# STEP-UP.net
KiCad netlist of a schematic drawn in Altium Designer
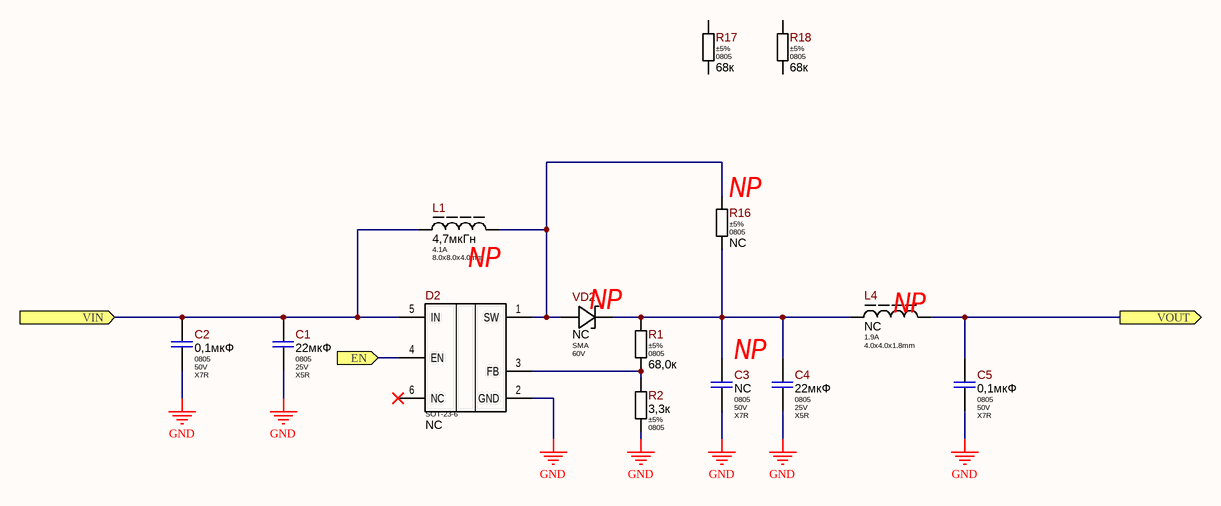
[diagram p0: STEP-UP.SchDoc]

(export (version "E")
  (design (tool "Eeschema 10.0.6"))
  (components
    (comp (ref "C1")
      (value "22мкФ")
      (footprint "CAP-0805(2012)X125T20")
      (description "22uF 25V X5R ±20% 0805 Ceramic Capacitor RoHS")
      (fields
        (field (name "PACKAGE") "0805")
        (field (name "VOLTAGE") "25V")
        (field (name "DIELECTRIC TYPE") "X5R")
        (field (name "PART NUMBER") "CL21A226MAYNNNE")
        (field (name "MANUFACTURER") "Samsung Electro-Mechanics")
      )
      (libsource (lib "capacitors") (part "CL21A226MAYNNNE"))
    )
    (comp (ref "C2")
      (value "0,1мкФ")
      (footprint "CAP-0805(2012)X85T10")
      (description "100nF 50V X7R ±10% 0805 Ceramic Capacitor RoHS")
      (fields
        (field (name "PACKAGE") "0805")
        (field (name "VOLTAGE") "50V")
        (field (name "DIELECTRIC TYPE") "X7R")
        (field (name "PART NUMBER") "CL21B104KBCNNNC")
        (field (name "MANUFACTURER") "Samsung Electro-Mechanics")
      )
      (libsource (lib "capacitors") (part "CL21B104KBCNNNC"))
    )
    (comp (ref "C3")
      (value "NC")
      (footprint "CAP-0805(2012)X85T10")
      (description "100nF 50V X7R ±10% 0805 Ceramic Capacitor RoHS")
      (fields
        (field (name "PACKAGE") "0805")
        (field (name "VOLTAGE") "50V")
        (field (name "DIELECTRIC TYPE") "X7R")
        (field (name "PART NUMBER") "CL21B104KBCNNNC")
        (field (name "MANUFACTURER") "Samsung Electro-Mechanics")
      )
      (libsource (lib "capacitors") (part "CL21B104KBCNNNC"))
    )
    (comp (ref "C4")
      (value "22мкФ")
      (footprint "CAP-0805(2012)X125T20")
      (description "22uF 25V X5R ±20% 0805 Ceramic Capacitor RoHS")
      (fields
        (field (name "PACKAGE") "0805")
        (field (name "VOLTAGE") "25V")
        (field (name "DIELECTRIC TYPE") "X5R")
        (field (name "PART NUMBER") "CL21A226MAYNNNE")
        (field (name "MANUFACTURER") "Samsung Electro-Mechanics")
      )
      (libsource (lib "capacitors") (part "CL21A226MAYNNNE"))
    )
    (comp (ref "C5")
      (value "0,1мкФ")
      (footprint "CAP-0805(2012)X85T10")
      (description "100nF 50V X7R ±10% 0805 Ceramic Capacitor RoHS")
      (fields
        (field (name "PACKAGE") "0805")
        (field (name "VOLTAGE") "50V")
        (field (name "DIELECTRIC TYPE") "X7R")
        (field (name "PART NUMBER") "CL21B104KBCNNNC")
        (field (name "MANUFACTURER") "Samsung Electro-Mechanics")
      )
      (libsource (lib "capacitors") (part "CL21B104KBCNNNC"))
    )
    (comp (ref "D2")
      (value "MT3608")
      (footprint "MT3608_MED")
      (description "2V-24V Input High Efficiency 1.2MHz 2A Step Up Converter")
      (fields
        (field (name "PACKAGE") "SOT-23-6")
        (field (name "PART NUMBER") "NC")
        (field (name "MANUFACTURER") "Aerosemi")
      )
      (libsource (lib "ic") (part "MT3608"))
    )
    (comp (ref "L1")
      (value "4,7мкГн")
      (footprint "SWPA8040S-Series")
      (description "4.7uH Magnetic-Resin Shielded Wirewound Inductor 4.1 A 25mOhm Max")
      (fields
        (field (name "CURRENT") "4.1A")
        (field (name "PACKAGE") "8.0x8.0x4.0mm")
        (field (name "PART NUMBER") "SWPA8040S4R7NT")
        (field (name "TOLERANCE") "±30%")
      )
      (libsource (lib "inductors") (part "SWPA8040S4R7NT"))
    )
    (comp (ref "L4")
      (value "NC")
      (footprint "SRN4018-Series_1.8mm")
      (description "4.7uH Semi-Shielded Wirewound Inductor 1.9A 84mOhm Max")
      (fields
        (field (name "CURRENT") "1.9A")
        (field (name "PACKAGE") "4.0x4.0x1.8mm")
        (field (name "PART NUMBER") "SRN4018-4R7M")
        (field (name "TOLERANCE") "±20%")
      )
      (libsource (lib "inductors") (part "SRN4018-4R7M"))
    )
    (comp (ref "R1")
      (value "68,0к")
      (footprint "R_ANY_CHIP_0805_MED")
      (description "2.2 kOhms ±5% 1/8W 0805 Thick Film Resistor")
      (fields
        (field (name "TOLERANCE") "±5%")
        (field (name "PACKAGE") "0805")
        (field (name "PART NUMBER") "RC0805JR-072K2L")
        (field (name "MANUFACTURER") "Yageo")
      )
      (libsource (lib "resistors") (part "RC0805JR-072K2L"))
    )
    (comp (ref "R2")
      (value "3,3к")
      (footprint "R_ANY_CHIP_0805_MED")
      (description "3.3 kOhms ±5%, 1/8W 0805 Thick Film Resistor")
      (fields
        (field (name "TOLERANCE") "±5%")
        (field (name "PACKAGE") "0805")
        (field (name "PART NUMBER") "RC0805JR-073K3L")
        (field (name "MANUFACTURER") "Yageo")
      )
      (libsource (lib "resistors") (part "RC0805JR-073K3L"))
    )
    (comp (ref "R16")
      (value "NC")
      (footprint "R_ANY_CHIP_0805_MED")
      (description "2.2 kOhms ±5% 1/8W 0805 Thick Film Resistor")
      (fields
        (field (name "TOLERANCE") "±5%")
        (field (name "PACKAGE") "0805")
        (field (name "PART NUMBER") "RC0805JR-072K2L")
        (field (name "MANUFACTURER") "Yageo")
      )
      (libsource (lib "resistors") (part "RC0805JR-072K2L"))
    )
    (comp (ref "R17")
      (value "68к")
      (footprint "R_ANY_CHIP_0805_MED")
      (description "2.2 kOhms ±5% 1/8W 0805 Thick Film Resistor")
      (fields
        (field (name "TOLERANCE") "±5%")
        (field (name "PACKAGE") "0805")
        (field (name "PART NUMBER") "RC0805JR-072K2L")
        (field (name "MANUFACTURER") "Yageo")
      )
      (libsource (lib "resistors") (part "RC0805JR-072K2L"))
    )
    (comp (ref "R18")
      (value "68к")
      (footprint "R_ANY_CHIP_0805_MED")
      (description "2.2 kOhms ±5% 1/8W 0805 Thick Film Resistor")
      (fields
        (field (name "TOLERANCE") "±5%")
        (field (name "PACKAGE") "0805")
        (field (name "PART NUMBER") "RC0805JR-072K2L")
        (field (name "MANUFACTURER") "Yageo")
      )
      (libsource (lib "resistors") (part "RC0805JR-072K2L"))
    )
    (comp (ref "VD2")
      (value "SK56A-LTP")
      (footprint "SMA_MED")
      (description "Diode Schottky 60V 5A, SMA")
      (fields
        (field (name "PART NUMBER") "NC")
        (field (name "PACKAGE") "SMA")
        (field (name "VOLTAGE") "60V")
        (field (name "MANUFACTURER") "Micro Commercial Components")
      )
      (libsource (lib "diodes") (part "SK56A-LTP"))
    )
  )
  (nets
    (net (code "1") (name "/EN") (class "Default")
      (node (ref "D2") (pin "4") (pinfunction "EN_4") (pintype "passive"))
    )
    (net (code "2") (name "/VIN") (class "Default")
      (node (ref "C1") (pin "1") (pinfunction "1_1") (pintype "passive"))
      (node (ref "C2") (pin "1") (pinfunction "1_1") (pintype "passive"))
      (node (ref "D2") (pin "5") (pinfunction "IN_5") (pintype "passive"))
      (node (ref "L1") (pin "1") (pintype "passive"))
    )
    (net (code "3") (name "/VOUT") (class "Default")
      (node (ref "C5") (pin "1") (pinfunction "1_1") (pintype "passive"))
      (node (ref "L4") (pin "2") (pintype "passive"))
    )
    (net (code "4") (name "GND") (class "Default")
      (node (ref "C1") (pin "2") (pinfunction "2_2") (pintype "passive"))
      (node (ref "C2") (pin "2") (pinfunction "2_2") (pintype "passive"))
      (node (ref "C3") (pin "2") (pinfunction "2_2") (pintype "passive"))
      (node (ref "C4") (pin "2") (pinfunction "2_2") (pintype "passive"))
      (node (ref "C5") (pin "2") (pinfunction "2_2") (pintype "passive"))
      (node (ref "D2") (pin "2") (pinfunction "GND_2") (pintype "passive"))
      (node (ref "R2") (pin "2") (pintype "passive"))
    )
    (net (code "5") (name "Net-(C3-Pad1)") (class "Default")
      (node (ref "C3") (pin "1") (pinfunction "1_1") (pintype "passive"))
      (node (ref "C4") (pin "1") (pinfunction "1_1") (pintype "passive"))
      (node (ref "L4") (pin "1") (pintype "passive"))
      (node (ref "R1") (pin "1") (pintype "passive"))
      (node (ref "R16") (pin "2") (pintype "passive"))
      (node (ref "VD2") (pin "CA") (pintype "passive"))
    )
    (net (code "6") (name "Net-(D2-FB)") (class "Default")
      (node (ref "D2") (pin "3") (pinfunction "FB_3") (pintype "passive"))
      (node (ref "R1") (pin "2") (pintype "passive"))
      (node (ref "R2") (pin "1") (pintype "passive"))
    )
    (net (code "7") (name "Net-(D2-SW)") (class "Default")
      (node (ref "D2") (pin "1") (pinfunction "SW_1") (pintype "passive"))
      (node (ref "L1") (pin "2") (pintype "passive"))
      (node (ref "R16") (pin "1") (pintype "passive"))
      (node (ref "VD2") (pin "AN") (pintype "passive"))
    )
    (net (code "8") (name "unconnected-(D2-NC-Pad6)") (class "Default")
      (node (ref "D2") (pin "6") (pinfunction "NC_6") (pintype "passive+no_connect"))
    )
    (net (code "9") (name "unconnected-(R17-Pad1)") (class "Default")
      (node (ref "R17") (pin "1") (pintype "passive"))
    )
    (net (code "10") (name "unconnected-(R17-Pad2)") (class "Default")
      (node (ref "R17") (pin "2") (pintype "passive"))
    )
    (net (code "11") (name "unconnected-(R18-Pad1)") (class "Default")
      (node (ref "R18") (pin "1") (pintype "passive"))
    )
    (net (code "12") (name "unconnected-(R18-Pad2)") (class "Default")
      (node (ref "R18") (pin "2") (pintype "passive"))
    )
  )
)
